# CAN_bus_powered.net
KiCad netlist of a schematic drawn in Altium Designer
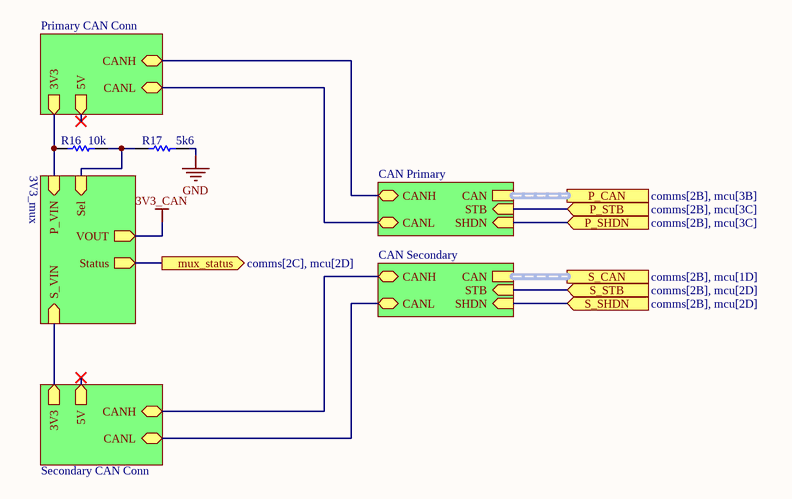
[diagram p0: CAN_bus_powered.SchDoc]

(export (version "E")
  (design (tool "Eeschema 10.0.6"))
  (components
    (comp (ref "R16")
      (value "10k")
      (description "Resistor")
      (libsource (lib "drfc_schlib") (part "Resistor"))
    )
    (comp (ref "R17")
      (value "5k6")
      (description "Resistor")
      (libsource (lib "drfc_schlib") (part "Resistor"))
    )
  )
  (nets
    (net (code "4") (name "/3V3_1") (class "Default")
      (node (ref "R16") (pin "2") (pinfunction "2_2") (pintype "passive"))
    )
    (net (code "17") (name "/Sel") (class "Default")
      (node (ref "R16") (pin "1") (pinfunction "1_1") (pintype "passive"))
      (node (ref "R17") (pin "2") (pinfunction "2_2") (pintype "passive"))
    )
    (net (code "20") (name "GND") (class "Default")
      (node (ref "R17") (pin "1") (pinfunction "1_1") (pintype "passive"))
    )
  )
)
